# VentaConnected_Arduino_V0_01_2017-11-25.net
KiCad netlist of a schematic drawn in EAGLE
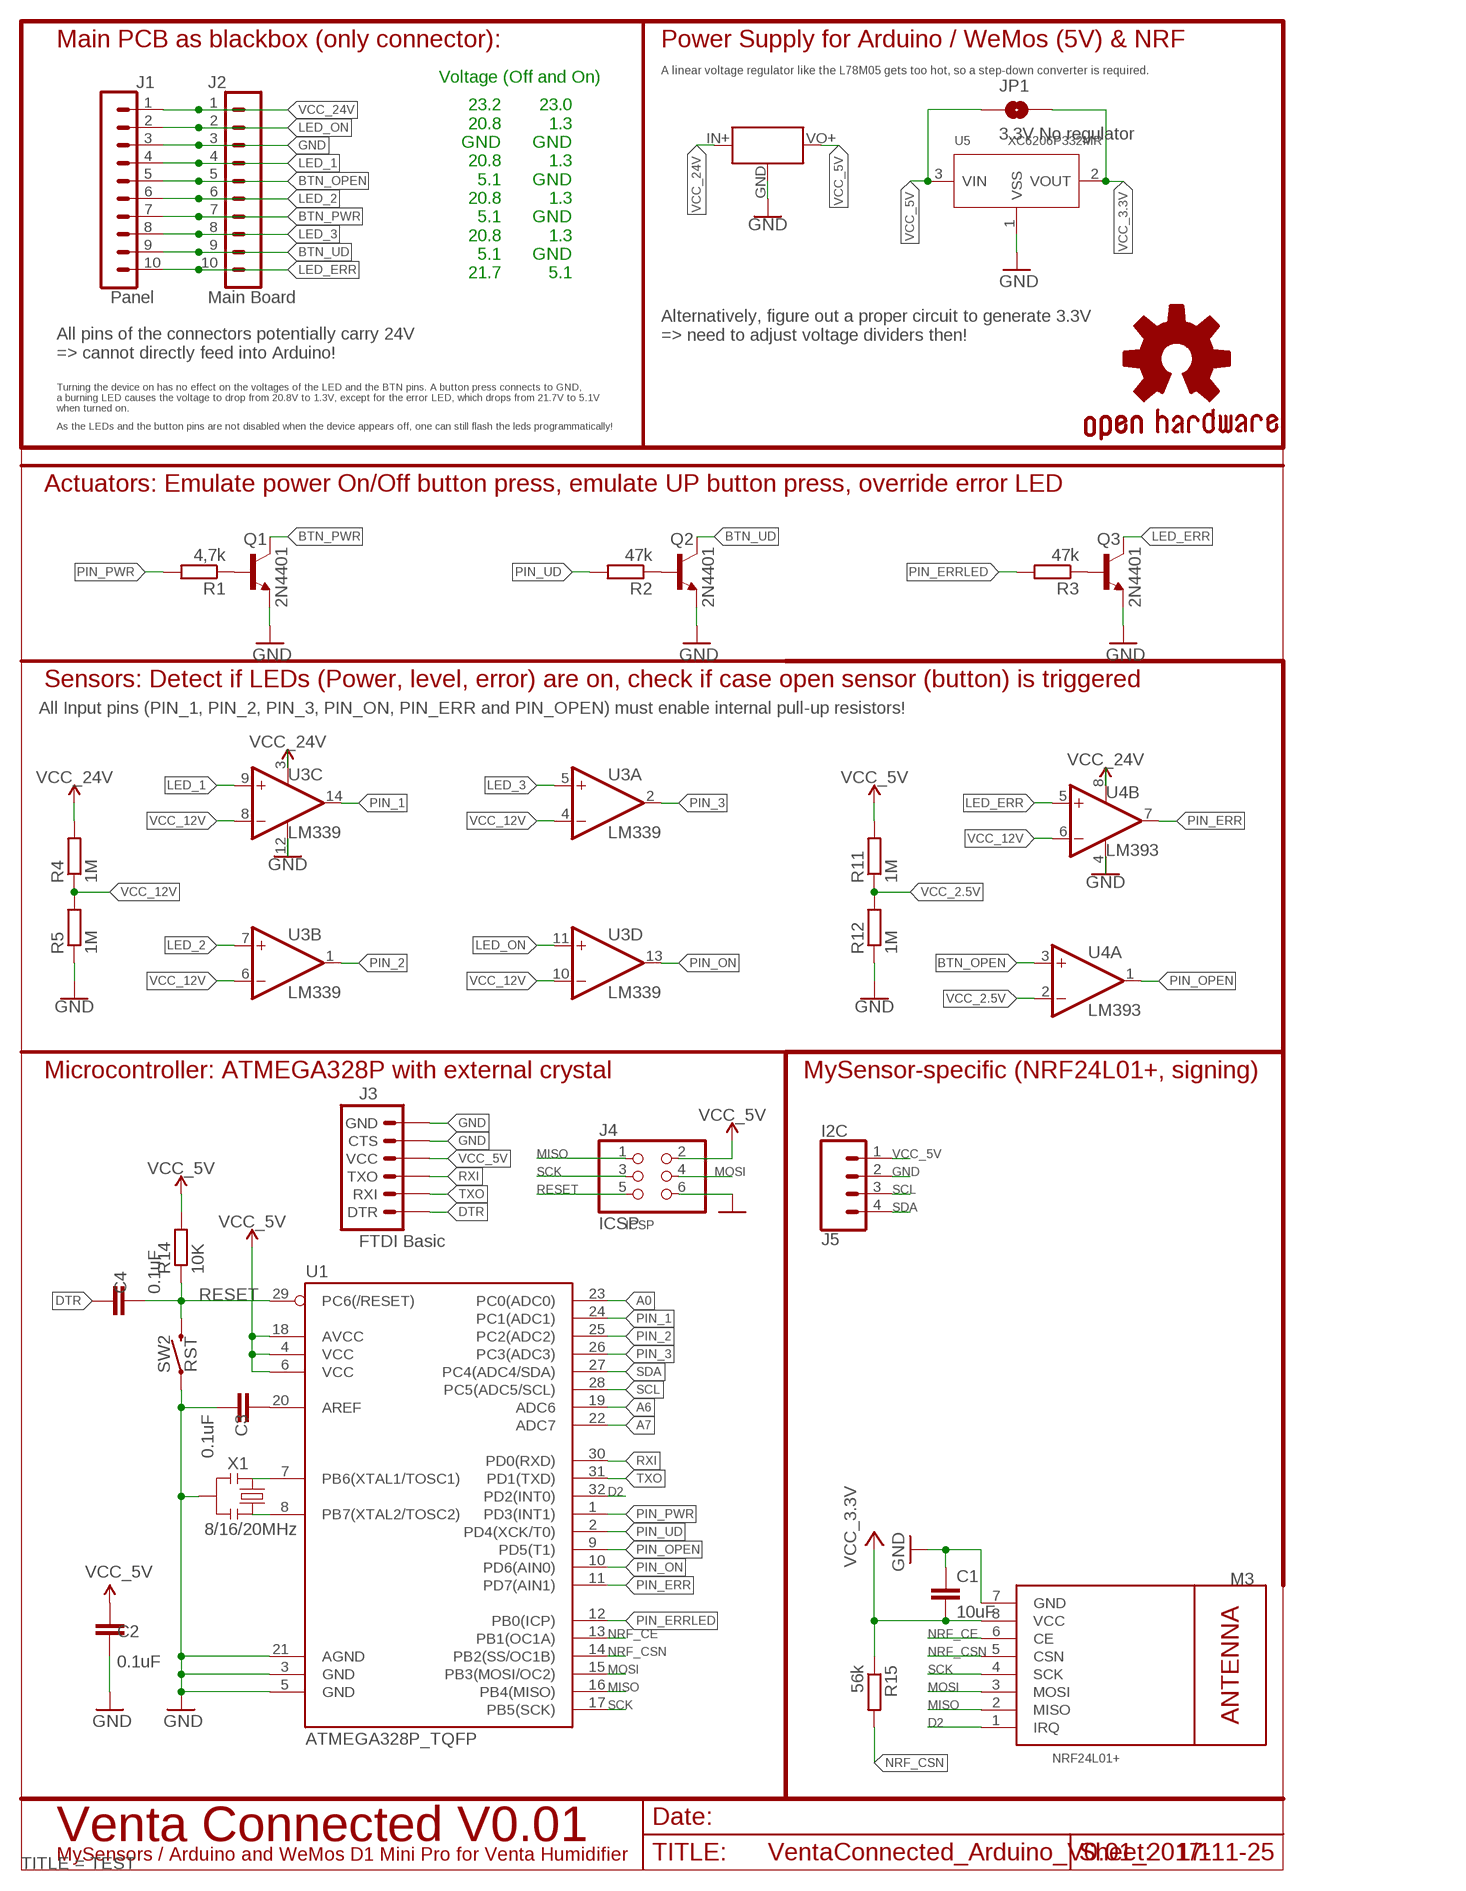
[diagram p0: schematic, sheet 1]

(export (version "E")
  (design (tool "Eeschema 10.0.6"))
  (components
    (comp (ref "C1")
      (value "10uF")
      (footprint "eagle-import:C0805")
      (libsource (lib "eagle-import") (part "C-EUC0805"))
    )
    (comp (ref "C2")
      (value "0.1uF")
      (footprint "eagle-import:C0805")
      (libsource (lib "eagle-import") (part "resistor_348_C-EUC0805"))
    )
    (comp (ref "C3")
      (value "0.1uF")
      (footprint "eagle-import:C0805")
      (libsource (lib "eagle-import") (part "resistor_348_C-EUC0805"))
    )
    (comp (ref "C4")
      (value "0.1uF")
      (footprint "eagle-import:C0805")
      (libsource (lib "eagle-import") (part "resistor_348_C-EUC0805"))
    )
    (comp (ref "GOLD_ORB_SM1")
      (value "OSHWLOGO_GOLD_ORB_SM")
      (footprint "eagle-import:OSHW2")
      (libsource (lib "eagle-import") (part "OSHWLOGO_GOLD_ORB_SM"))
    )
    (comp (ref "J1")
      (value "Panel")
      (footprint "eagle-import:2X5-SHROUDED")
      (libsource (lib "eagle-import") (part "CONN_05X2SHD"))
    )
    (comp (ref "J2")
      (value "Main Board")
      (footprint "eagle-import:2X5")
      (libsource (lib "eagle-import") (part "CONN_05X2PTH"))
    )
    (comp (ref "J3")
      (value "FTDI Basic")
      (footprint "eagle-import:1X06")
      (libsource (lib "eagle-import") (part "ARDUINO_SERIAL_PROGRAMPTH"))
    )
    (comp (ref "J4")
      (value "ICSP")
      (footprint "eagle-import:2X03")
      (libsource (lib "eagle-import") (part "PINHD-2X3"))
    )
    (comp (ref "J5")
      (value "I2C")
      (footprint "eagle-import:1X04")
      (libsource (lib "eagle-import") (part "CONN_04"))
    )
    (comp (ref "JP1")
      (value "3.3V No regulator")
      (footprint "eagle-import:SMT-JUMPER_2_NO_SILK")
      (libsource (lib "eagle-import") (part "JUMPER-SMT_2_NO_SILK"))
    )
    (comp (ref "M3")
      (value "NRF24L01+")
      (footprint "eagle-import:WIRELESS-NRF24L01-SMD")
      (libsource (lib "eagle-import") (part "WIRELESS-NRF24L01SMD"))
    )
    (comp (ref "Q1")
      (value "2N4401")
      (footprint "eagle-import:SOT23-BEC")
      (libsource (lib "eagle-import") (part "-NPN-SOT23-BECMMBT4401LT1"))
    )
    (comp (ref "Q2")
      (value "2N4401")
      (footprint "eagle-import:SOT23-BEC")
      (libsource (lib "eagle-import") (part "-NPN-SOT23-BECMMBT4401LT1"))
    )
    (comp (ref "Q3")
      (value "2N4401")
      (footprint "eagle-import:SOT23-BEC")
      (libsource (lib "eagle-import") (part "-NPN-SOT23-BECMMBT4401LT1"))
    )
    (comp (ref "R1")
      (value "4,7k")
      (footprint "eagle-import:R0805")
      (libsource (lib "eagle-import") (part "resistor_348_R-EU_R0805"))
    )
    (comp (ref "R2")
      (value "47k")
      (footprint "eagle-import:R0805")
      (libsource (lib "eagle-import") (part "resistor_348_R-EU_R0805"))
    )
    (comp (ref "R3")
      (value "47k")
      (footprint "eagle-import:R0805")
      (libsource (lib "eagle-import") (part "resistor_348_R-EU_R0805"))
    )
    (comp (ref "R4")
      (value "1M")
      (footprint "eagle-import:R0805")
      (libsource (lib "eagle-import") (part "resistor_348_R-EU_R0805"))
    )
    (comp (ref "R5")
      (value "1M")
      (footprint "eagle-import:R0805")
      (libsource (lib "eagle-import") (part "resistor_348_R-EU_R0805"))
    )
    (comp (ref "R11")
      (value "1M")
      (footprint "eagle-import:R0805")
      (libsource (lib "eagle-import") (part "resistor_348_R-EU_R0805"))
    )
    (comp (ref "R12")
      (value "1M")
      (footprint "eagle-import:R0805")
      (libsource (lib "eagle-import") (part "resistor_348_R-EU_R0805"))
    )
    (comp (ref "R14")
      (value "10K")
      (footprint "eagle-import:R0805")
      (libsource (lib "eagle-import") (part "rcl_334_R-EU_R0805"))
    )
    (comp (ref "R15")
      (value "56k")
      (footprint "eagle-import:R0805")
      (libsource (lib "eagle-import") (part "R-EU_R0805"))
    )
    (comp (ref "SW2")
      (value "RST")
      (footprint "eagle-import:TACTILE_SWITCH_SMD_6.0X3.5MM")
      (libsource (lib "eagle-import") (part "MOMENTARY-SWITCH-SPST-SMD-6.0X3.5MM"))
    )
    (comp (ref "U1")
      (value "ATMEGA328P_TQFP")
      (footprint "eagle-import:TQFP32-08")
      (libsource (lib "eagle-import") (part "ATMEGA328P_TQFP"))
    )
    (comp (ref "U2")
      (value "MINI_BUCK_CONVERTER_UPSIDEDOWN")
      (footprint "eagle-import:MINI_BUCK_CONVERTER_UPDOWN")
      (libsource (lib "eagle-import") (part "MINI_BUCK_CONVERTER_UPSIDEDOWN"))
    )
    (comp (ref "U3")
      (value "LM339")
      (footprint "eagle-import:SO14")
      (libsource (lib "eagle-import") (part "TLC339D"))
    )
    (comp (ref "U4")
      (value "LM393")
      (footprint "eagle-import:SO08")
      (libsource (lib "eagle-import") (part "LM393D"))
    )
    (comp (ref "U5")
      (value "XC6206P332MR")
      (footprint "eagle-import:SOT-23")
      (fields (field (name "MPN") "XC6206P332MR-G"))
      (libsource (lib "eagle-import") (part "PMIC-LDO-XC6206P332MR-G(SOT23)"))
    )
    (comp (ref "X1")
      (value "8/16/20MHz")
      (footprint "eagle-import:RESONATOR-SMD-1_1")
      (libsource (lib "eagle-import") (part "RESONATOR1{colon}1"))
    )
  )
  (nets
    (net (code "1") (name "/D2") (class "Default")
      (node (ref "M3") (pin "1") (pinfunction "IRQ_1") (pintype "bidirectional"))
      (node (ref "U1") (pin "32") (pinfunction "PD2(INT0)_32") (pintype "bidirectional"))
    )
    (net (code "2") (name "/MISO") (class "Default")
      (node (ref "J4") (pin "1") (pinfunction "1_1") (pintype "passive"))
      (node (ref "M3") (pin "2") (pinfunction "MISO_2") (pintype "bidirectional"))
      (node (ref "U1") (pin "16") (pinfunction "PB4(MISO)_16") (pintype "bidirectional"))
    )
    (net (code "3") (name "/MOSI") (class "Default")
      (node (ref "J4") (pin "4") (pinfunction "4_4") (pintype "passive"))
      (node (ref "M3") (pin "3") (pinfunction "MOSI_3") (pintype "bidirectional"))
      (node (ref "U1") (pin "15") (pinfunction "PB3(MOSI/OC2)_15") (pintype "bidirectional"))
    )
    (net (code "4") (name "/NRF_CE") (class "Default")
      (node (ref "M3") (pin "6") (pinfunction "CE_6") (pintype "bidirectional"))
      (node (ref "U1") (pin "13") (pinfunction "PB1(OC1A)_13") (pintype "bidirectional"))
    )
    (net (code "5") (name "/RESET") (class "Default")
      (node (ref "C4") (pin "1") (pinfunction "1_1") (pintype "passive"))
      (node (ref "J4") (pin "5") (pinfunction "5_5") (pintype "passive"))
      (node (ref "R14") (pin "1") (pinfunction "1_1") (pintype "passive"))
      (node (ref "SW2") (pin "2") (pinfunction "2_2") (pintype "passive"))
      (node (ref "U1") (pin "29") (pinfunction "PC6(/RESET)_29") (pintype "bidirectional"))
    )
    (net (code "6") (name "/SCK") (class "Default")
      (node (ref "J4") (pin "3") (pinfunction "3_3") (pintype "passive"))
      (node (ref "M3") (pin "4") (pinfunction "SCK_4") (pintype "bidirectional"))
      (node (ref "U1") (pin "17") (pinfunction "PB5(SCK)_17") (pintype "bidirectional"))
    )
    (net (code "7") (name "A0") (class "Default")
      (node (ref "U1") (pin "23") (pinfunction "PC0(ADC0)_23") (pintype "bidirectional"))
    )
    (net (code "8") (name "A6") (class "Default")
      (node (ref "U1") (pin "19") (pinfunction "ADC6_19") (pintype "bidirectional"))
    )
    (net (code "9") (name "A7") (class "Default")
      (node (ref "U1") (pin "22") (pinfunction "ADC7_22") (pintype "bidirectional"))
    )
    (net (code "10") (name "BTN_OPEN") (class "Default")
      (node (ref "J1") (pin "5") (pinfunction "5_5") (pintype "passive"))
      (node (ref "J2") (pin "5") (pinfunction "5_5") (pintype "passive"))
      (node (ref "U4") (pin "3") (pinfunction "+IN_3") (pintype "input"))
    )
    (net (code "11") (name "BTN_PWR") (class "Default")
      (node (ref "J1") (pin "7") (pinfunction "7_7") (pintype "passive"))
      (node (ref "J2") (pin "7") (pinfunction "7_7") (pintype "passive"))
      (node (ref "Q1") (pin "C") (pinfunction "C_C") (pintype "passive"))
    )
    (net (code "12") (name "BTN_UD") (class "Default")
      (node (ref "J1") (pin "9") (pinfunction "9_9") (pintype "passive"))
      (node (ref "J2") (pin "9") (pinfunction "9_9") (pintype "passive"))
      (node (ref "Q2") (pin "C") (pinfunction "C_C") (pintype "passive"))
    )
    (net (code "13") (name "DTR") (class "Default")
      (node (ref "C4") (pin "2") (pinfunction "2_2") (pintype "passive"))
      (node (ref "J3") (pin "1") (pinfunction "DTR_1") (pintype "passive"))
    )
    (net (code "14") (name "GND") (class "Default")
      (node (ref "C1") (pin "1") (pinfunction "1_1") (pintype "passive"))
      (node (ref "C2") (pin "1") (pinfunction "1_1") (pintype "passive"))
      (node (ref "C3") (pin "1") (pinfunction "1_1") (pintype "passive"))
      (node (ref "J1") (pin "3") (pinfunction "3_3") (pintype "passive"))
      (node (ref "J2") (pin "3") (pinfunction "3_3") (pintype "passive"))
      (node (ref "J3") (pin "5") (pinfunction "CTS_5") (pintype "passive"))
      (node (ref "J3") (pin "6") (pinfunction "GND_6") (pintype "passive"))
      (node (ref "J4") (pin "6") (pinfunction "6_6") (pintype "passive"))
      (node (ref "J5") (pin "2") (pinfunction "2_2") (pintype "passive"))
      (node (ref "M3") (pin "7") (pinfunction "GND_7") (pintype "power_in"))
      (node (ref "Q1") (pin "E") (pinfunction "E_E") (pintype "passive"))
      (node (ref "Q2") (pin "E") (pinfunction "E_E") (pintype "passive"))
      (node (ref "Q3") (pin "E") (pinfunction "E_E") (pintype "passive"))
      (node (ref "R12") (pin "1") (pinfunction "1_1") (pintype "passive"))
      (node (ref "R5") (pin "1") (pinfunction "1_1") (pintype "passive"))
      (node (ref "SW2") (pin "1") (pinfunction "1_1") (pintype "passive"))
      (node (ref "U1") (pin "21") (pinfunction "AGND_21") (pintype "bidirectional"))
      (node (ref "U1") (pin "3") (pinfunction "GND_3") (pintype "bidirectional"))
      (node (ref "U1") (pin "5") (pinfunction "GND_5") (pintype "bidirectional"))
      (node (ref "U2") (pin "GND") (pinfunction "GND_GND") (pintype "bidirectional"))
      (node (ref "U3") (pin "12") (pinfunction "V-_12") (pintype "power_in"))
      (node (ref "U4") (pin "4") (pinfunction "V-_4") (pintype "power_in"))
      (node (ref "U5") (pin "1") (pinfunction "VSS_1") (pintype "power_in"))
      (node (ref "X1") (pin "2") (pinfunction "2_2") (pintype "passive"))
    )
    (net (code "15") (name "LED_1") (class "Default")
      (node (ref "J1") (pin "4") (pinfunction "4_4") (pintype "passive"))
      (node (ref "J2") (pin "4") (pinfunction "4_4") (pintype "passive"))
      (node (ref "U3") (pin "9") (pinfunction "+IN_9") (pintype "input"))
    )
    (net (code "16") (name "LED_2") (class "Default")
      (node (ref "J1") (pin "6") (pinfunction "6_6") (pintype "passive"))
      (node (ref "J2") (pin "6") (pinfunction "6_6") (pintype "passive"))
      (node (ref "U3") (pin "7") (pinfunction "+IN_7") (pintype "input"))
    )
    (net (code "17") (name "LED_3") (class "Default")
      (node (ref "J1") (pin "8") (pinfunction "8_8") (pintype "passive"))
      (node (ref "J2") (pin "8") (pinfunction "8_8") (pintype "passive"))
      (node (ref "U3") (pin "5") (pinfunction "+IN_5") (pintype "input"))
    )
    (net (code "18") (name "LED_ERR") (class "Default")
      (node (ref "J1") (pin "10") (pinfunction "10_10") (pintype "passive"))
      (node (ref "J2") (pin "10") (pinfunction "10_10") (pintype "passive"))
      (node (ref "Q3") (pin "C") (pinfunction "C_C") (pintype "passive"))
      (node (ref "U4") (pin "5") (pinfunction "+IN_5") (pintype "input"))
    )
    (net (code "19") (name "LED_ON") (class "Default")
      (node (ref "J1") (pin "2") (pinfunction "2_2") (pintype "passive"))
      (node (ref "J2") (pin "2") (pinfunction "2_2") (pintype "passive"))
      (node (ref "U3") (pin "11") (pinfunction "+IN_11") (pintype "input"))
    )
    (net (code "20") (name "NRF_CSN") (class "Default")
      (node (ref "M3") (pin "5") (pinfunction "CSN_5") (pintype "bidirectional"))
      (node (ref "R15") (pin "2") (pinfunction "2_2") (pintype "passive"))
      (node (ref "U1") (pin "14") (pinfunction "PB2(SS/OC1B)_14") (pintype "bidirectional"))
    )
    (net (code "21") (name "Net-(Q1-PadB)") (class "Default")
      (node (ref "Q1") (pin "B") (pinfunction "B_B") (pintype "passive"))
      (node (ref "R1") (pin "1") (pinfunction "1_1") (pintype "passive"))
    )
    (net (code "22") (name "Net-(Q2-PadB)") (class "Default")
      (node (ref "Q2") (pin "B") (pinfunction "B_B") (pintype "passive"))
      (node (ref "R2") (pin "1") (pinfunction "1_1") (pintype "passive"))
    )
    (net (code "23") (name "Net-(Q3-PadB)") (class "Default")
      (node (ref "Q3") (pin "B") (pinfunction "B_B") (pintype "passive"))
      (node (ref "R3") (pin "1") (pinfunction "1_1") (pintype "passive"))
    )
    (net (code "24") (name "Net-(U1-AREF)") (class "Default")
      (node (ref "C3") (pin "2") (pinfunction "2_2") (pintype "passive"))
      (node (ref "U1") (pin "20") (pinfunction "AREF_20") (pintype "bidirectional"))
    )
    (net (code "25") (name "Net-(U1-PB6(XTAL1{slash}TOSC1))") (class "Default")
      (node (ref "U1") (pin "7") (pinfunction "PB6(XTAL1/TOSC1)_7") (pintype "bidirectional"))
      (node (ref "X1") (pin "1") (pinfunction "1_1") (pintype "passive"))
    )
    (net (code "26") (name "Net-(U1-PB7(XTAL2{slash}TOSC2))") (class "Default")
      (node (ref "U1") (pin "8") (pinfunction "PB7(XTAL2/TOSC2)_8") (pintype "bidirectional"))
      (node (ref "X1") (pin "3") (pinfunction "3_3") (pintype "passive"))
    )
    (net (code "27") (name "PIN_1") (class "Default")
      (node (ref "U1") (pin "24") (pinfunction "PC1(ADC1)_24") (pintype "bidirectional"))
      (node (ref "U3") (pin "14") (pinfunction "OUT_14") (pintype "output"))
    )
    (net (code "28") (name "PIN_2") (class "Default")
      (node (ref "U1") (pin "25") (pinfunction "PC2(ADC2)_25") (pintype "bidirectional"))
      (node (ref "U3") (pin "1") (pinfunction "OUT_1") (pintype "output"))
    )
    (net (code "29") (name "PIN_3") (class "Default")
      (node (ref "U1") (pin "26") (pinfunction "PC3(ADC3)_26") (pintype "bidirectional"))
      (node (ref "U3") (pin "2") (pinfunction "OUT_2") (pintype "output"))
    )
    (net (code "30") (name "PIN_ERR") (class "Default")
      (node (ref "U1") (pin "11") (pinfunction "PD7(AIN1)_11") (pintype "bidirectional"))
      (node (ref "U4") (pin "7") (pinfunction "OUT_7") (pintype "output"))
    )
    (net (code "31") (name "PIN_ERRLED") (class "Default")
      (node (ref "R3") (pin "2") (pinfunction "2_2") (pintype "passive"))
      (node (ref "U1") (pin "12") (pinfunction "PB0(ICP)_12") (pintype "bidirectional"))
    )
    (net (code "32") (name "PIN_ON") (class "Default")
      (node (ref "U1") (pin "10") (pinfunction "PD6(AIN0)_10") (pintype "bidirectional"))
      (node (ref "U3") (pin "13") (pinfunction "OUT_13") (pintype "output"))
    )
    (net (code "33") (name "PIN_OPEN") (class "Default")
      (node (ref "U1") (pin "9") (pinfunction "PD5(T1)_9") (pintype "bidirectional"))
      (node (ref "U4") (pin "1") (pinfunction "OUT_1") (pintype "output"))
    )
    (net (code "34") (name "PIN_PWR") (class "Default")
      (node (ref "R1") (pin "2") (pinfunction "2_2") (pintype "passive"))
      (node (ref "U1") (pin "1") (pinfunction "PD3(INT1)_1") (pintype "bidirectional"))
    )
    (net (code "35") (name "PIN_UD") (class "Default")
      (node (ref "R2") (pin "2") (pinfunction "2_2") (pintype "passive"))
      (node (ref "U1") (pin "2") (pinfunction "PD4(XCK/T0)_2") (pintype "bidirectional"))
    )
    (net (code "36") (name "RXI") (class "Default")
      (node (ref "J3") (pin "3") (pinfunction "TXO_3") (pintype "passive"))
      (node (ref "U1") (pin "30") (pinfunction "PD0(RXD)_30") (pintype "bidirectional"))
    )
    (net (code "37") (name "SCL") (class "Default")
      (node (ref "J5") (pin "3") (pinfunction "3_3") (pintype "passive"))
      (node (ref "U1") (pin "28") (pinfunction "PC5(ADC5/SCL)_28") (pintype "bidirectional"))
    )
    (net (code "38") (name "SDA") (class "Default")
      (node (ref "J5") (pin "4") (pinfunction "4_4") (pintype "passive"))
      (node (ref "U1") (pin "27") (pinfunction "PC4(ADC4/SDA)_27") (pintype "bidirectional"))
    )
    (net (code "39") (name "TXO") (class "Default")
      (node (ref "J3") (pin "2") (pinfunction "RXI_2") (pintype "passive"))
      (node (ref "U1") (pin "31") (pinfunction "PD1(TXD)_31") (pintype "bidirectional"))
    )
    (net (code "40") (name "VCC_2.5V") (class "Default")
      (node (ref "R11") (pin "1") (pinfunction "1_1") (pintype "passive"))
      (node (ref "R12") (pin "2") (pinfunction "2_2") (pintype "passive"))
      (node (ref "U4") (pin "2") (pinfunction "-IN_2") (pintype "input"))
    )
    (net (code "41") (name "VCC_3.3V") (class "Default")
      (node (ref "C1") (pin "2") (pinfunction "2_2") (pintype "passive"))
      (node (ref "JP1") (pin "2") (pinfunction "2_2") (pintype "passive"))
      (node (ref "M3") (pin "8") (pinfunction "VCC_8") (pintype "power_in"))
      (node (ref "R15") (pin "1") (pinfunction "1_1") (pintype "passive"))
      (node (ref "U5") (pin "2") (pinfunction "VOUT_2") (pintype "output"))
    )
    (net (code "42") (name "VCC_5V") (class "Default")
      (node (ref "C2") (pin "2") (pinfunction "2_2") (pintype "passive"))
      (node (ref "J3") (pin "4") (pinfunction "VCC_4") (pintype "passive"))
      (node (ref "J4") (pin "2") (pinfunction "2_2") (pintype "passive"))
      (node (ref "J5") (pin "1") (pinfunction "1_1") (pintype "passive"))
      (node (ref "JP1") (pin "1") (pinfunction "1_1") (pintype "passive"))
      (node (ref "R11") (pin "2") (pinfunction "2_2") (pintype "passive"))
      (node (ref "R14") (pin "2") (pinfunction "2_2") (pintype "passive"))
      (node (ref "U1") (pin "18") (pinfunction "AVCC_18") (pintype "bidirectional"))
      (node (ref "U1") (pin "4") (pinfunction "VCC_4") (pintype "bidirectional"))
      (node (ref "U1") (pin "6") (pinfunction "VCC_6") (pintype "bidirectional"))
      (node (ref "U2") (pin "VO+") (pinfunction "VOUT_VO+") (pintype "power_in"))
      (node (ref "U5") (pin "3") (pinfunction "VIN_3") (pintype "input"))
    )
    (net (code "43") (name "VCC_12V") (class "Default")
      (node (ref "R4") (pin "1") (pinfunction "1_1") (pintype "passive"))
      (node (ref "R5") (pin "2") (pinfunction "2_2") (pintype "passive"))
      (node (ref "U3") (pin "10") (pinfunction "-IN_10") (pintype "input"))
      (node (ref "U3") (pin "4") (pinfunction "-IN_4") (pintype "input"))
      (node (ref "U3") (pin "6") (pinfunction "-IN_6") (pintype "input"))
      (node (ref "U3") (pin "8") (pinfunction "-IN_8") (pintype "input"))
      (node (ref "U4") (pin "6") (pinfunction "-IN_6") (pintype "input"))
    )
    (net (code "44") (name "VCC_24V") (class "Default")
      (node (ref "J1") (pin "1") (pinfunction "1_1") (pintype "passive"))
      (node (ref "J2") (pin "1") (pinfunction "1_1") (pintype "passive"))
      (node (ref "R4") (pin "2") (pinfunction "2_2") (pintype "passive"))
      (node (ref "U2") (pin "IN+") (pinfunction "VIN_IN+") (pintype "input"))
      (node (ref "U3") (pin "3") (pinfunction "V+_3") (pintype "power_in"))
      (node (ref "U4") (pin "8") (pinfunction "V+_8") (pintype "power_in"))
    )
  )
)
